# 644-alt-layout-routed.net
KiCad netlist of a schematic drawn in EAGLE
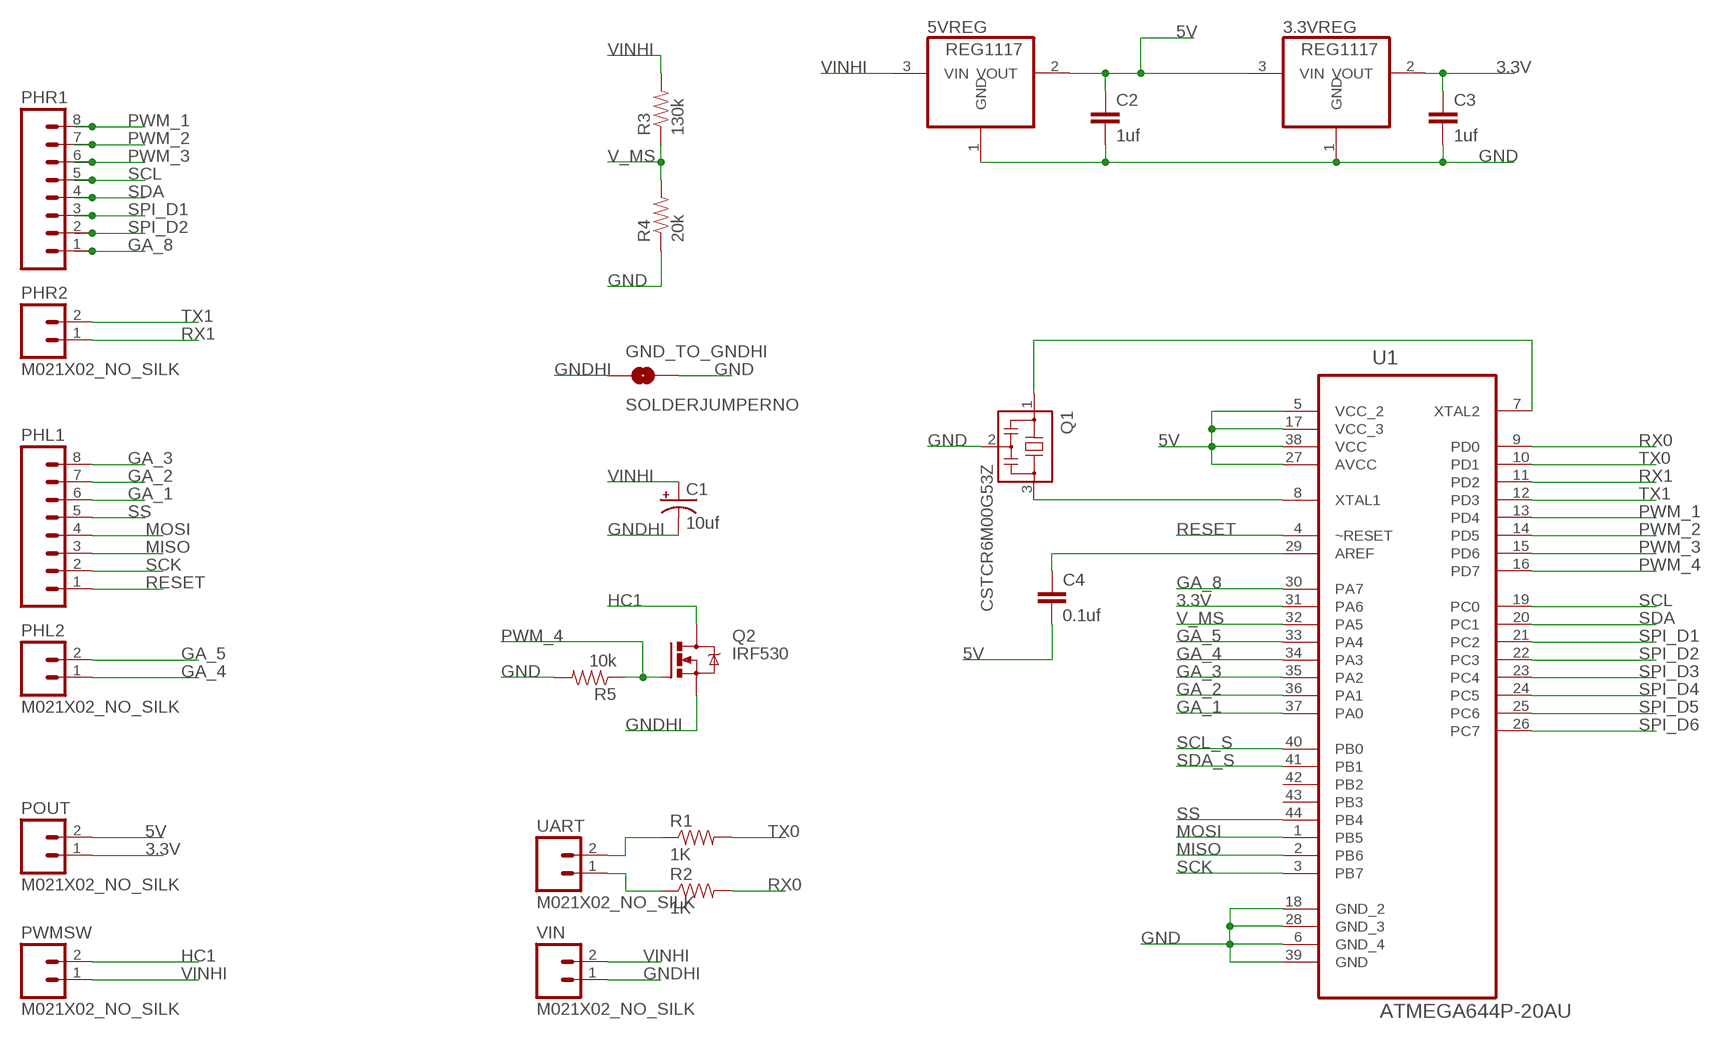
[diagram p0: schematic, sheet 1]

(export (version "E")
  (design (tool "Eeschema 10.0.6"))
  (components
    (comp (ref "3.3VREG")
      (value "REG1117")
      (footprint "eagle-import:SOT223")
      (libsource (lib "eagle-import") (part "REG1117"))
    )
    (comp (ref "5VREG")
      (value "REG1117")
      (footprint "eagle-import:SOT223")
      (libsource (lib "eagle-import") (part "REG1117"))
    )
    (comp (ref "C1")
      (value "10uf")
      (footprint "eagle-import:EIA3216")
      (libsource (lib "eagle-import") (part "CAP_POL1206"))
    )
    (comp (ref "C2")
      (value "1uf")
      (footprint "eagle-import:0603-CAP")
      (libsource (lib "eagle-import") (part "CAP0603-CAP"))
    )
    (comp (ref "C3")
      (value "1uf")
      (footprint "eagle-import:0603-CAP")
      (libsource (lib "eagle-import") (part "CAP0603-CAP"))
    )
    (comp (ref "C4")
      (value "0.1uf")
      (footprint "eagle-import:0603-CAP")
      (libsource (lib "eagle-import") (part "CAP0603-CAP"))
    )
    (comp (ref "GND_TO_GNDHI")
      (value "SOLDERJUMPERNO")
      (footprint "eagle-import:SJ_2S-NO")
      (libsource (lib "eagle-import") (part "SOLDERJUMPERNO"))
    )
    (comp (ref "PHL1")
      (value "M08NO_SILK")
      (footprint "eagle-import:1X08_PIN1_NO_SILK")
      (libsource (lib "eagle-import") (part "M08NO_SILK"))
    )
    (comp (ref "PHL2")
      (value "M021X02_NO_SILK")
      (footprint "eagle-import:1X02_NO_SILK")
      (libsource (lib "eagle-import") (part "M021X02_NO_SILK"))
    )
    (comp (ref "PHR1")
      (value "M08NO_SILK")
      (footprint "eagle-import:1X08_PIN1_NO_SILK")
      (libsource (lib "eagle-import") (part "M08NO_SILK"))
    )
    (comp (ref "PHR2")
      (value "M021X02_NO_SILK")
      (footprint "eagle-import:1X02_NO_SILK")
      (libsource (lib "eagle-import") (part "M021X02_NO_SILK"))
    )
    (comp (ref "POUT")
      (value "M021X02_NO_SILK")
      (footprint "eagle-import:1X02_NO_SILK")
      (libsource (lib "eagle-import") (part "M021X02_NO_SILK"))
    )
    (comp (ref "PWMSW")
      (value "M021X02_NO_SILK")
      (footprint "eagle-import:1X02_NO_SILK")
      (libsource (lib "eagle-import") (part "M021X02_NO_SILK"))
    )
    (comp (ref "Q1")
      (value "CSTCR6M00G53Z")
      (footprint "eagle-import:CSTCR6M")
      (fields (field (name "MPN") "CSTCR6M00G53-R0"))
      (libsource (lib "eagle-import") (part "CSTCR6M00G53Z"))
    )
    (comp (ref "Q2")
      (value "IRF530")
      (footprint "eagle-import:TO220BV")
      (libsource (lib "eagle-import") (part "IRF530"))
    )
    (comp (ref "R1")
      (value "1K")
      (footprint "eagle-import:0603-RES")
      (libsource (lib "eagle-import") (part "RESISTOR0603-RES"))
    )
    (comp (ref "R2")
      (value "1K")
      (footprint "eagle-import:0603-RES")
      (libsource (lib "eagle-import") (part "RESISTOR0603-RES"))
    )
    (comp (ref "R3")
      (value "130k")
      (footprint "eagle-import:0603-RES")
      (libsource (lib "eagle-import") (part "RESISTOR0603-RES"))
    )
    (comp (ref "R4")
      (value "20k")
      (footprint "eagle-import:0603-RES")
      (libsource (lib "eagle-import") (part "RESISTOR0603-RES"))
    )
    (comp (ref "R5")
      (value "10k")
      (footprint "eagle-import:0603-RES")
      (libsource (lib "eagle-import") (part "RESISTOR0603-RES"))
    )
    (comp (ref "U1")
      (value "ATMEGA644P-20AU")
      (footprint "eagle-import:QFP80P1200X1200X120-44N")
      (libsource (lib "eagle-import") (part "ATMEGA644P-20AU"))
    )
    (comp (ref "UART")
      (value "M021X02_NO_SILK")
      (footprint "eagle-import:1X02_NO_SILK")
      (libsource (lib "eagle-import") (part "M021X02_NO_SILK"))
    )
    (comp (ref "VIN")
      (value "M021X02_NO_SILK")
      (footprint "eagle-import:1X02_NO_SILK")
      (libsource (lib "eagle-import") (part "M021X02_NO_SILK"))
    )
  )
  (nets
    (net (code "1") (name "/3.3V") (class "Default")
      (node (ref "3.3VREG") (pin "2") (pinfunction "VOUT_2") (pintype "output"))
      (node (ref "C3") (pin "1") (pinfunction "1_1") (pintype "passive"))
      (node (ref "POUT") (pin "1") (pinfunction "1_1") (pintype "passive"))
      (node (ref "U1") (pin "31") (pinfunction "PA6_31") (pintype "bidirectional"))
    )
    (net (code "2") (name "/5V") (class "Default")
      (node (ref "3.3VREG") (pin "3") (pinfunction "VIN_3") (pintype "input"))
      (node (ref "5VREG") (pin "2") (pinfunction "VOUT_2") (pintype "output"))
      (node (ref "C2") (pin "1") (pinfunction "1_1") (pintype "passive"))
      (node (ref "C4") (pin "2") (pinfunction "2_2") (pintype "passive"))
      (node (ref "POUT") (pin "2") (pinfunction "2_2") (pintype "passive"))
      (node (ref "U1") (pin "17") (pinfunction "VCC_3_17") (pintype "power_in"))
      (node (ref "U1") (pin "27") (pinfunction "AVCC_27") (pintype "power_in"))
      (node (ref "U1") (pin "38") (pinfunction "VCC_38") (pintype "power_in"))
      (node (ref "U1") (pin "5") (pinfunction "VCC_2_5") (pintype "power_in"))
    )
    (net (code "3") (name "/GA_1") (class "Default")
      (node (ref "PHL1") (pin "6") (pinfunction "6_6") (pintype "passive"))
      (node (ref "U1") (pin "37") (pinfunction "PA0_37") (pintype "bidirectional"))
    )
    (net (code "4") (name "/GA_2") (class "Default")
      (node (ref "PHL1") (pin "7") (pinfunction "7_7") (pintype "passive"))
      (node (ref "U1") (pin "36") (pinfunction "PA1_36") (pintype "bidirectional"))
    )
    (net (code "5") (name "/GA_3") (class "Default")
      (node (ref "PHL1") (pin "8") (pinfunction "8_8") (pintype "passive"))
      (node (ref "U1") (pin "35") (pinfunction "PA2_35") (pintype "bidirectional"))
    )
    (net (code "6") (name "/GA_4") (class "Default")
      (node (ref "PHL2") (pin "1") (pinfunction "1_1") (pintype "passive"))
      (node (ref "U1") (pin "34") (pinfunction "PA3_34") (pintype "bidirectional"))
    )
    (net (code "7") (name "/GA_5") (class "Default")
      (node (ref "PHL2") (pin "2") (pinfunction "2_2") (pintype "passive"))
      (node (ref "U1") (pin "33") (pinfunction "PA4_33") (pintype "bidirectional"))
    )
    (net (code "8") (name "/GA_8") (class "Default")
      (node (ref "PHR1") (pin "1") (pinfunction "1_1") (pintype "passive"))
      (node (ref "U1") (pin "30") (pinfunction "PA7_30") (pintype "bidirectional"))
    )
    (net (code "9") (name "/GND") (class "Default")
      (node (ref "3.3VREG") (pin "1") (pinfunction "GND_1") (pintype "power_in"))
      (node (ref "5VREG") (pin "1") (pinfunction "GND_1") (pintype "power_in"))
      (node (ref "C2") (pin "2") (pinfunction "2_2") (pintype "passive"))
      (node (ref "C3") (pin "2") (pinfunction "2_2") (pintype "passive"))
      (node (ref "GND_TO_GNDHI") (pin "2") (pinfunction "2_2") (pintype "passive"))
      (node (ref "Q1") (pin "2") (pinfunction "2_2") (pintype "passive"))
      (node (ref "R4") (pin "1") (pinfunction "1_1") (pintype "passive"))
      (node (ref "R5") (pin "2") (pinfunction "2_2") (pintype "passive"))
      (node (ref "U1") (pin "18") (pinfunction "GND_2_18") (pintype "passive"))
      (node (ref "U1") (pin "28") (pinfunction "GND_3_28") (pintype "passive"))
      (node (ref "U1") (pin "39") (pinfunction "GND_39") (pintype "passive"))
      (node (ref "U1") (pin "6") (pinfunction "GND_4_6") (pintype "passive"))
    )
    (net (code "10") (name "/GNDHI") (class "Default")
      (node (ref "C1") (pin "C") (pinfunction "-_C") (pintype "passive"))
      (node (ref "GND_TO_GNDHI") (pin "1") (pinfunction "1_1") (pintype "passive"))
      (node (ref "Q2") (pin "S") (pinfunction "S_S") (pintype "passive"))
      (node (ref "VIN") (pin "1") (pinfunction "1_1") (pintype "passive"))
    )
    (net (code "11") (name "/HC1") (class "Default")
      (node (ref "PWMSW") (pin "2") (pinfunction "2_2") (pintype "passive"))
      (node (ref "Q2") (pin "D") (pinfunction "D_D") (pintype "passive"))
    )
    (net (code "12") (name "/MISO") (class "Default")
      (node (ref "PHL1") (pin "3") (pinfunction "3_3") (pintype "passive"))
      (node (ref "U1") (pin "2") (pinfunction "PB6_2") (pintype "bidirectional"))
    )
    (net (code "13") (name "/MOSI") (class "Default")
      (node (ref "PHL1") (pin "4") (pinfunction "4_4") (pintype "passive"))
      (node (ref "U1") (pin "1") (pinfunction "PB5_1") (pintype "bidirectional"))
    )
    (net (code "14") (name "/PWM_1") (class "Default")
      (node (ref "PHR1") (pin "8") (pinfunction "8_8") (pintype "passive"))
      (node (ref "U1") (pin "13") (pinfunction "PD4_13") (pintype "bidirectional"))
    )
    (net (code "15") (name "/PWM_2") (class "Default")
      (node (ref "PHR1") (pin "7") (pinfunction "7_7") (pintype "passive"))
      (node (ref "U1") (pin "14") (pinfunction "PD5_14") (pintype "bidirectional"))
    )
    (net (code "16") (name "/PWM_3") (class "Default")
      (node (ref "PHR1") (pin "6") (pinfunction "6_6") (pintype "passive"))
      (node (ref "U1") (pin "15") (pinfunction "PD6_15") (pintype "bidirectional"))
    )
    (net (code "17") (name "/PWM_4") (class "Default")
      (node (ref "Q2") (pin "G") (pinfunction "G_G") (pintype "passive"))
      (node (ref "R5") (pin "1") (pinfunction "1_1") (pintype "passive"))
      (node (ref "U1") (pin "16") (pinfunction "PD7_16") (pintype "bidirectional"))
    )
    (net (code "18") (name "/RESET") (class "Default")
      (node (ref "PHL1") (pin "1") (pinfunction "1_1") (pintype "passive"))
      (node (ref "U1") (pin "4") (pinfunction "~{RESET}_4") (pintype "input"))
    )
    (net (code "19") (name "/RX0") (class "Default")
      (node (ref "R2") (pin "2") (pinfunction "2_2") (pintype "passive"))
      (node (ref "U1") (pin "9") (pinfunction "PD0_9") (pintype "bidirectional"))
    )
    (net (code "20") (name "/RX1") (class "Default")
      (node (ref "PHR2") (pin "1") (pinfunction "1_1") (pintype "passive"))
      (node (ref "U1") (pin "11") (pinfunction "PD2_11") (pintype "bidirectional"))
    )
    (net (code "21") (name "/SCK") (class "Default")
      (node (ref "PHL1") (pin "2") (pinfunction "2_2") (pintype "passive"))
      (node (ref "U1") (pin "3") (pinfunction "PB7_3") (pintype "bidirectional"))
    )
    (net (code "22") (name "/SCL") (class "Default")
      (node (ref "PHR1") (pin "5") (pinfunction "5_5") (pintype "passive"))
      (node (ref "U1") (pin "19") (pinfunction "PC0_19") (pintype "bidirectional"))
    )
    (net (code "23") (name "/SCL_S") (class "Default")
      (node (ref "U1") (pin "40") (pinfunction "PB0_40") (pintype "bidirectional"))
    )
    (net (code "24") (name "/SDA") (class "Default")
      (node (ref "PHR1") (pin "4") (pinfunction "4_4") (pintype "passive"))
      (node (ref "U1") (pin "20") (pinfunction "PC1_20") (pintype "bidirectional"))
    )
    (net (code "25") (name "/SDA_S") (class "Default")
      (node (ref "U1") (pin "41") (pinfunction "PB1_41") (pintype "bidirectional"))
    )
    (net (code "26") (name "/SPI_D1") (class "Default")
      (node (ref "PHR1") (pin "3") (pinfunction "3_3") (pintype "passive"))
      (node (ref "U1") (pin "21") (pinfunction "PC2_21") (pintype "bidirectional"))
    )
    (net (code "27") (name "/SPI_D2") (class "Default")
      (node (ref "PHR1") (pin "2") (pinfunction "2_2") (pintype "passive"))
      (node (ref "U1") (pin "22") (pinfunction "PC3_22") (pintype "bidirectional"))
    )
    (net (code "28") (name "/SPI_D3") (class "Default")
      (node (ref "U1") (pin "23") (pinfunction "PC4_23") (pintype "bidirectional"))
    )
    (net (code "29") (name "/SPI_D4") (class "Default")
      (node (ref "U1") (pin "24") (pinfunction "PC5_24") (pintype "bidirectional"))
    )
    (net (code "30") (name "/SPI_D5") (class "Default")
      (node (ref "U1") (pin "25") (pinfunction "PC6_25") (pintype "bidirectional"))
    )
    (net (code "31") (name "/SPI_D6") (class "Default")
      (node (ref "U1") (pin "26") (pinfunction "PC7_26") (pintype "bidirectional"))
    )
    (net (code "32") (name "/SS") (class "Default")
      (node (ref "PHL1") (pin "5") (pinfunction "5_5") (pintype "passive"))
      (node (ref "U1") (pin "44") (pinfunction "PB4_44") (pintype "bidirectional"))
    )
    (net (code "33") (name "/TX0") (class "Default")
      (node (ref "R1") (pin "2") (pinfunction "2_2") (pintype "passive"))
      (node (ref "U1") (pin "10") (pinfunction "PD1_10") (pintype "bidirectional"))
    )
    (net (code "34") (name "/TX1") (class "Default")
      (node (ref "PHR2") (pin "2") (pinfunction "2_2") (pintype "passive"))
      (node (ref "U1") (pin "12") (pinfunction "PD3_12") (pintype "bidirectional"))
    )
    (net (code "35") (name "/VINHI") (class "Default")
      (node (ref "5VREG") (pin "3") (pinfunction "VIN_3") (pintype "input"))
      (node (ref "C1") (pin "A") (pinfunction "+_A") (pintype "passive"))
      (node (ref "PWMSW") (pin "1") (pinfunction "1_1") (pintype "passive"))
      (node (ref "R3") (pin "2") (pinfunction "2_2") (pintype "passive"))
      (node (ref "VIN") (pin "2") (pinfunction "2_2") (pintype "passive"))
    )
    (net (code "36") (name "/V_MS") (class "Default")
      (node (ref "R3") (pin "1") (pinfunction "1_1") (pintype "passive"))
      (node (ref "R4") (pin "2") (pinfunction "2_2") (pintype "passive"))
      (node (ref "U1") (pin "32") (pinfunction "PA5_32") (pintype "bidirectional"))
    )
    (net (code "37") (name "Net-(R1-Pad1)") (class "Default")
      (node (ref "R1") (pin "1") (pinfunction "1_1") (pintype "passive"))
      (node (ref "UART") (pin "2") (pinfunction "2_2") (pintype "passive"))
    )
    (net (code "38") (name "Net-(R2-Pad1)") (class "Default")
      (node (ref "R2") (pin "1") (pinfunction "1_1") (pintype "passive"))
      (node (ref "UART") (pin "1") (pinfunction "1_1") (pintype "passive"))
    )
    (net (code "39") (name "Net-(U1-AREF)") (class "Default")
      (node (ref "C4") (pin "1") (pinfunction "1_1") (pintype "passive"))
      (node (ref "U1") (pin "29") (pinfunction "AREF_29") (pintype "input"))
    )
    (net (code "40") (name "Net-(U1-XTAL1)") (class "Default")
      (node (ref "Q1") (pin "3") (pinfunction "3_3") (pintype "passive"))
      (node (ref "U1") (pin "8") (pinfunction "XTAL1_8") (pintype "input"))
    )
    (net (code "41") (name "Net-(U1-XTAL2)") (class "Default")
      (node (ref "Q1") (pin "1") (pinfunction "1_1") (pintype "passive"))
      (node (ref "U1") (pin "7") (pinfunction "XTAL2_7") (pintype "output"))
    )
    (net (code "42") (name "unconnected-(U1-PB2-Pad42)") (class "Default")
      (node (ref "U1") (pin "42") (pinfunction "PB2_42") (pintype "bidirectional"))
    )
    (net (code "43") (name "unconnected-(U1-PB3-Pad43)") (class "Default")
      (node (ref "U1") (pin "43") (pinfunction "PB3_43") (pintype "bidirectional"))
    )
  )
)
